# Quad512K.net
KiCad netlist of a schematic drawn in EAGLE
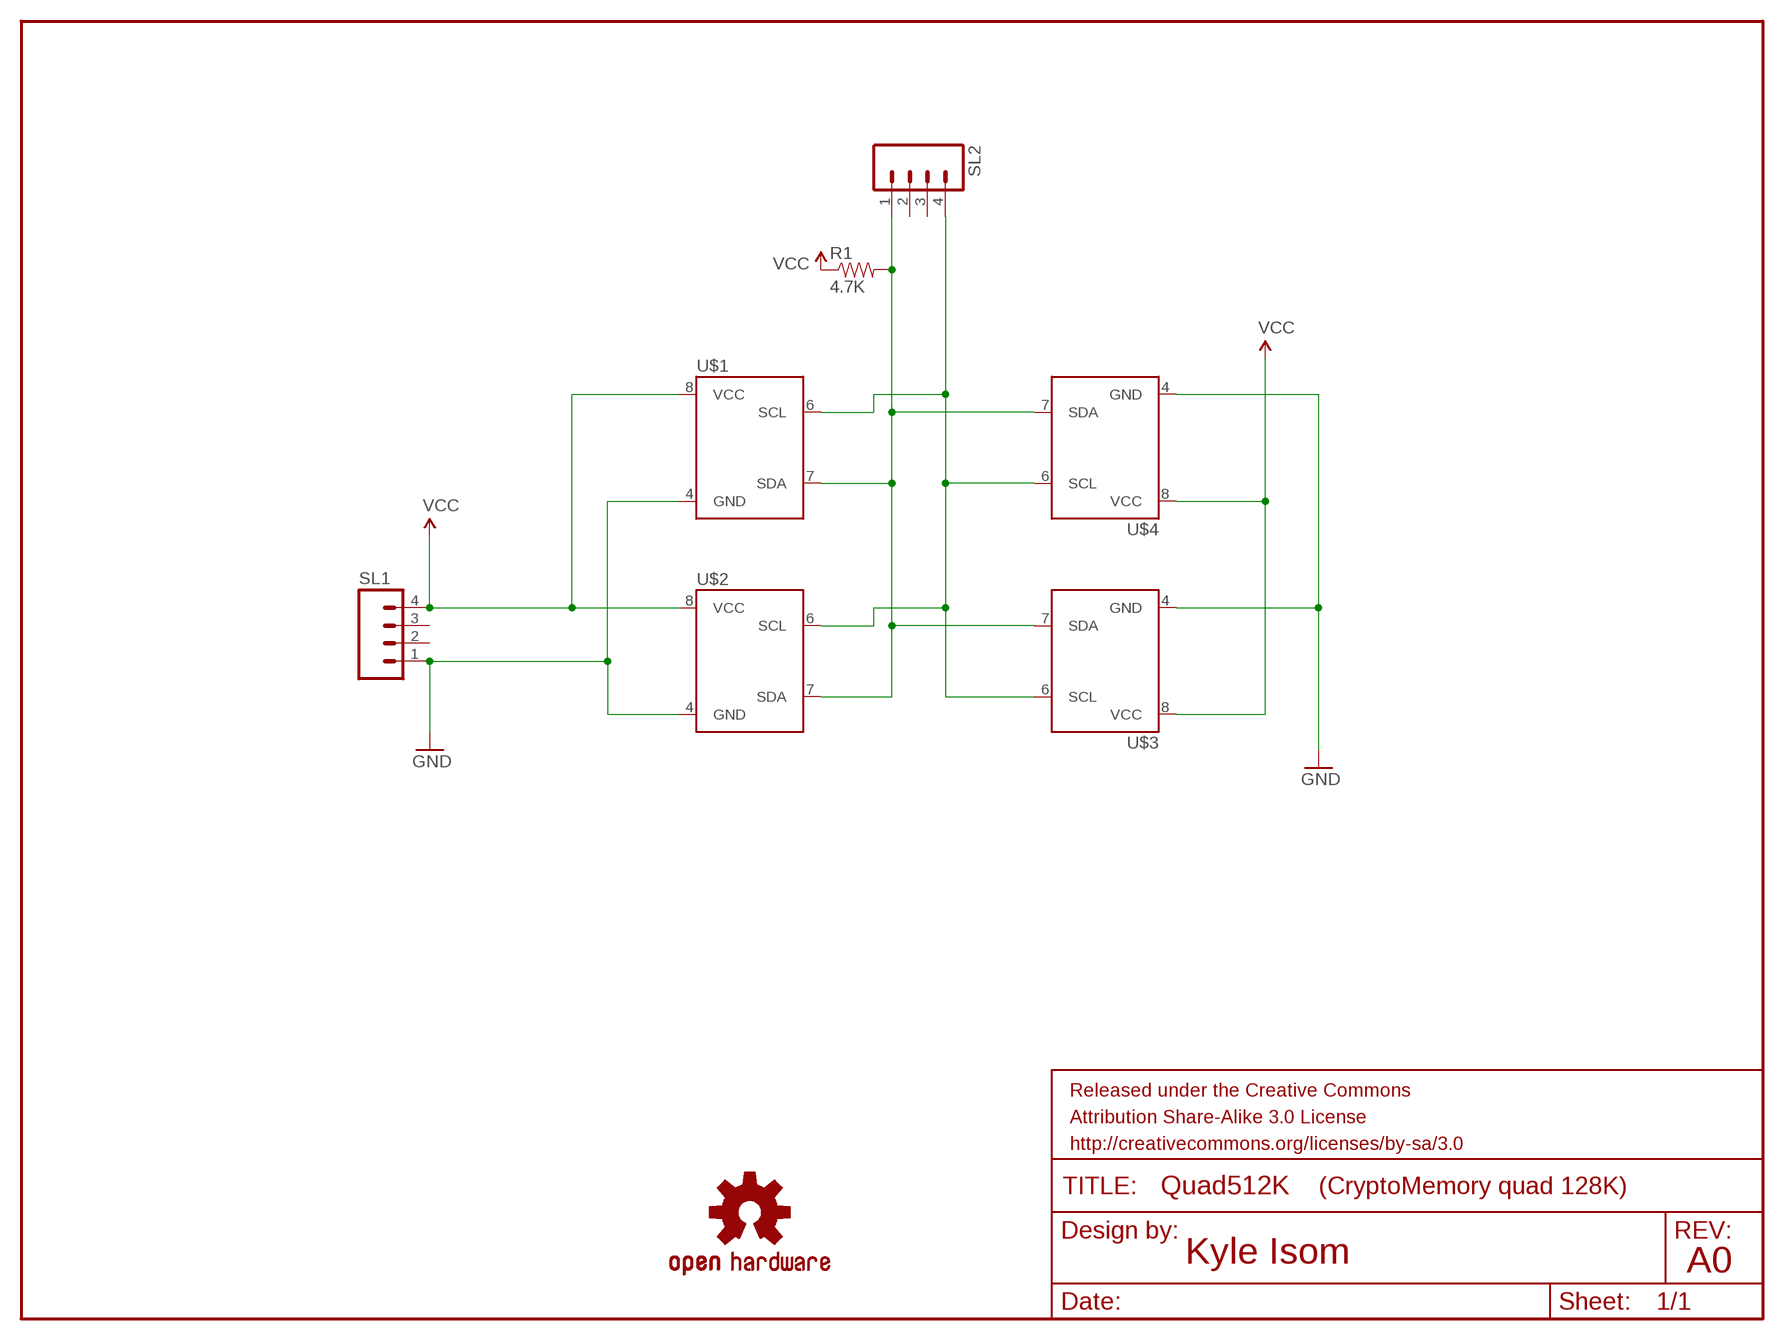
[diagram p0: schematic, sheet 1]

(export (version "E")
  (design (tool "Eeschema 10.0.6"))
  (components
    (comp (ref "FRAME1")
      (value "FRAME-LETTER")
      (footprint "eagle-import:CREATIVE_COMMONS")
      (libsource (lib "eagle-import") (part "FRAME-LETTER"))
    )
    (comp (ref "LOGO1")
      (value "OSHW-LOGOS")
      (footprint "eagle-import:OSHW-LOGO-S")
      (libsource (lib "eagle-import") (part "OSHW-LOGOS"))
    )
    (comp (ref "R1")
      (value "4.7K")
      (footprint "eagle-import:AXIAL-0.4")
      (libsource (lib "eagle-import") (part "RESISTORPTH-1/4W"))
    )
    (comp (ref "SL1")
      (value "M04LOCK")
      (footprint "eagle-import:1X04_LOCK")
      (libsource (lib "eagle-import") (part "M04LOCK"))
    )
    (comp (ref "SL2")
      (value "M04LOCK")
      (footprint "eagle-import:1X04_LOCK")
      (libsource (lib "eagle-import") (part "M04LOCK"))
    )
    (comp (ref "U$1")
      (value "AT88SCAT88SC-PDIP")
      (footprint "eagle-import:DIL08")
      (libsource (lib "eagle-import") (part "AT88SCAT88SC-PDIP"))
    )
    (comp (ref "U$2")
      (value "AT88SCAT88SC-PDIP")
      (footprint "eagle-import:DIL08")
      (libsource (lib "eagle-import") (part "AT88SCAT88SC-PDIP"))
    )
    (comp (ref "U$3")
      (value "AT88SCAT88SC-PDIP")
      (footprint "eagle-import:DIL08")
      (libsource (lib "eagle-import") (part "AT88SCAT88SC-PDIP"))
    )
    (comp (ref "U$4")
      (value "AT88SCAT88SC-PDIP")
      (footprint "eagle-import:DIL08")
      (libsource (lib "eagle-import") (part "AT88SCAT88SC-PDIP"))
    )
  )
  (nets
    (net (code "1") (name "GND") (class "Default")
      (node (ref "SL1") (pin "1") (pinfunction "1_1") (pintype "passive"))
      (node (ref "U$1") (pin "4") (pinfunction "GND_4") (pintype "power_in"))
      (node (ref "U$2") (pin "4") (pinfunction "GND_4") (pintype "power_in"))
      (node (ref "U$3") (pin "4") (pinfunction "GND_4") (pintype "power_in"))
      (node (ref "U$4") (pin "4") (pinfunction "GND_4") (pintype "power_in"))
    )
    (net (code "2") (name "Net-(R1-2)") (class "Default")
      (node (ref "R1") (pin "P$2") (pinfunction "2_P$2") (pintype "passive"))
      (node (ref "SL2") (pin "1") (pinfunction "1_1") (pintype "passive"))
      (node (ref "U$1") (pin "7") (pinfunction "SDA_7") (pintype "bidirectional"))
      (node (ref "U$2") (pin "7") (pinfunction "SDA_7") (pintype "bidirectional"))
      (node (ref "U$3") (pin "7") (pinfunction "SDA_7") (pintype "bidirectional"))
      (node (ref "U$4") (pin "7") (pinfunction "SDA_7") (pintype "bidirectional"))
    )
    (net (code "3") (name "Net-(U$1-SCL)") (class "Default")
      (node (ref "SL2") (pin "4") (pinfunction "4_4") (pintype "passive"))
      (node (ref "U$1") (pin "6") (pinfunction "SCL_6") (pintype "bidirectional"))
      (node (ref "U$2") (pin "6") (pinfunction "SCL_6") (pintype "bidirectional"))
      (node (ref "U$3") (pin "6") (pinfunction "SCL_6") (pintype "bidirectional"))
      (node (ref "U$4") (pin "6") (pinfunction "SCL_6") (pintype "bidirectional"))
    )
    (net (code "4") (name "VCC") (class "Default")
      (node (ref "R1") (pin "P$1") (pinfunction "1_P$1") (pintype "passive"))
      (node (ref "SL1") (pin "4") (pinfunction "4_4") (pintype "passive"))
      (node (ref "U$1") (pin "8") (pinfunction "VCC_8") (pintype "power_in"))
      (node (ref "U$2") (pin "8") (pinfunction "VCC_8") (pintype "power_in"))
      (node (ref "U$3") (pin "8") (pinfunction "VCC_8") (pintype "power_in"))
      (node (ref "U$4") (pin "8") (pinfunction "VCC_8") (pintype "power_in"))
    )
    (net (code "5") (name "unconnected-(SL1-Pad2)") (class "Default")
      (node (ref "SL1") (pin "2") (pinfunction "2_2") (pintype "passive"))
    )
    (net (code "6") (name "unconnected-(SL1-Pad3)") (class "Default")
      (node (ref "SL1") (pin "3") (pinfunction "3_3") (pintype "passive"))
    )
    (net (code "7") (name "unconnected-(SL2-Pad2)") (class "Default")
      (node (ref "SL2") (pin "2") (pinfunction "2_2") (pintype "passive"))
    )
    (net (code "8") (name "unconnected-(SL2-Pad3)") (class "Default")
      (node (ref "SL2") (pin "3") (pinfunction "3_3") (pintype "passive"))
    )
  )
)
